# lumysens.net
KiCad netlist of a schematic drawn in EAGLE
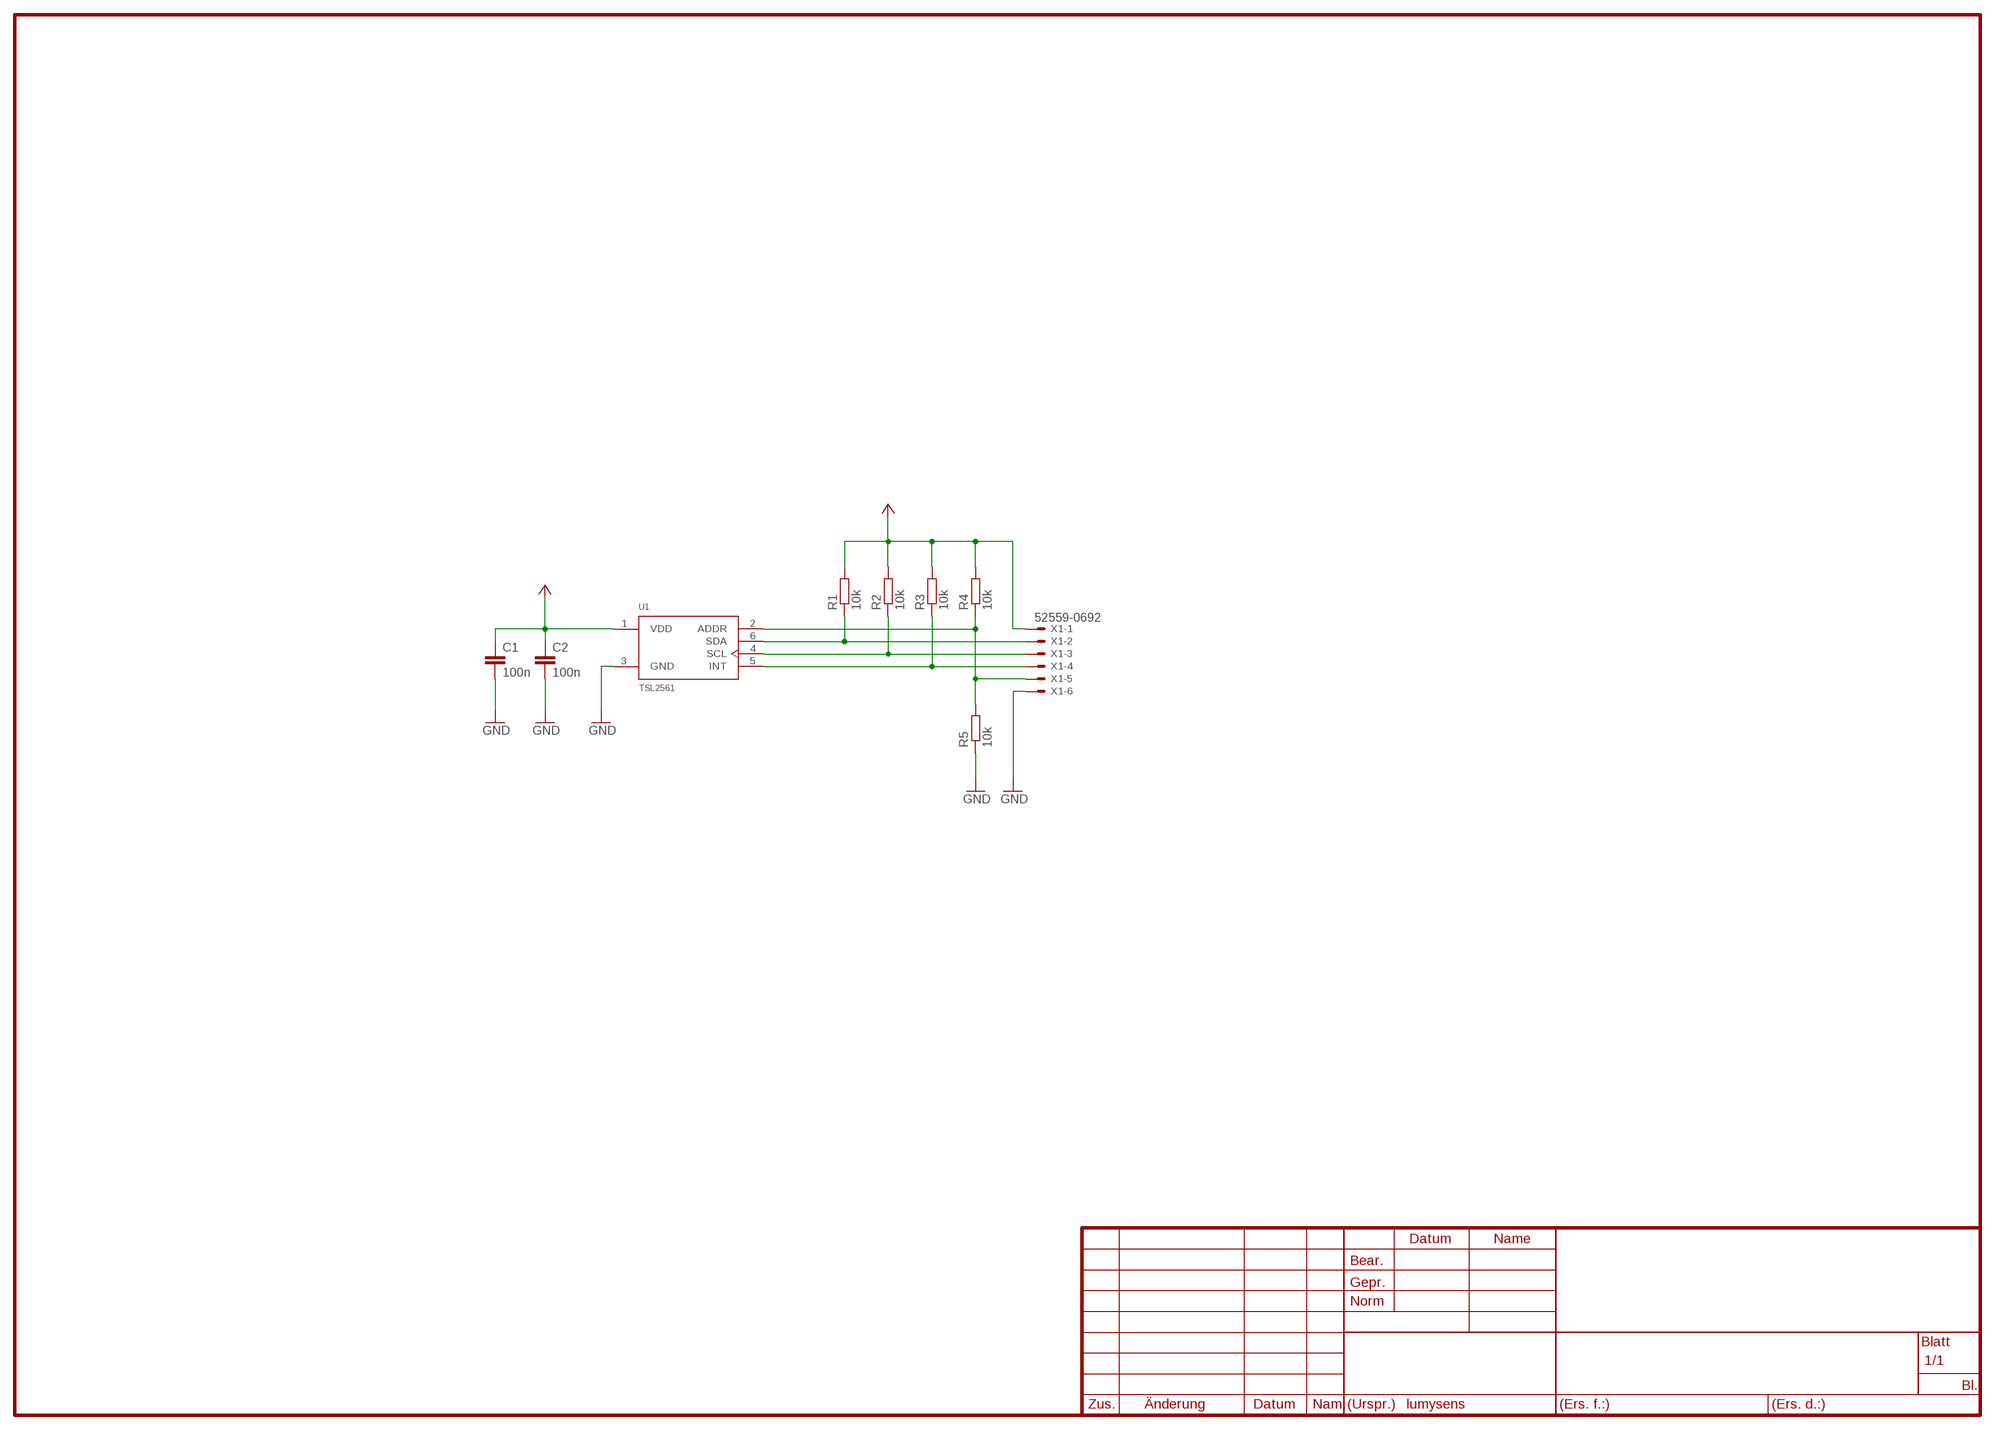
[diagram p0: schematic, sheet 1]

(export (version "E")
  (design (tool "Eeschema 10.0.6"))
  (components
    (comp (ref "C1")
      (value "100n")
      (footprint "eagle-import:C0603")
      (libsource (lib "eagle-import") (part "C-EUC0603"))
    )
    (comp (ref "C2")
      (value "100n")
      (footprint "eagle-import:C0603")
      (libsource (lib "eagle-import") (part "C-EUC0603"))
    )
    (comp (ref "R1")
      (value "10k")
      (footprint "eagle-import:R0603")
      (libsource (lib "eagle-import") (part "R-EU_R0603"))
    )
    (comp (ref "R2")
      (value "10k")
      (footprint "eagle-import:R0603")
      (libsource (lib "eagle-import") (part "R-EU_R0603"))
    )
    (comp (ref "R3")
      (value "10k")
      (footprint "eagle-import:R0603")
      (libsource (lib "eagle-import") (part "R-EU_R0603"))
    )
    (comp (ref "R4")
      (value "10k")
      (footprint "eagle-import:R0603")
      (libsource (lib "eagle-import") (part "R-EU_R0603"))
    )
    (comp (ref "R5")
      (value "10k")
      (footprint "eagle-import:R0603")
      (libsource (lib "eagle-import") (part "R-EU_R0603"))
    )
    (comp (ref "U1")
      (value "TSL2561")
      (footprint "eagle-import:TMB-6")
      (libsource (lib "eagle-import") (part "TSL2561"))
    )
    (comp (ref "X1")
      (value "52559-0692")
      (footprint "eagle-import:52559-0692")
      (libsource (lib "eagle-import") (part "52559-0692"))
    )
  )
  (nets
    (net (code "1") (name "GND") (class "Default")
      (node (ref "C1") (pin "2") (pinfunction "2_2") (pintype "passive"))
      (node (ref "C2") (pin "2") (pinfunction "2_2") (pintype "passive"))
      (node (ref "R5") (pin "1") (pinfunction "1_1") (pintype "passive"))
      (node (ref "U1") (pin "3") (pinfunction "GND_3") (pintype "power_in"))
      (node (ref "X1") (pin "6") (pinfunction "S_6") (pintype "passive"))
    )
    (net (code "2") (name "Net-(U1-ADDR)") (class "Default")
      (node (ref "R4") (pin "1") (pinfunction "1_1") (pintype "passive"))
      (node (ref "R5") (pin "2") (pinfunction "2_2") (pintype "passive"))
      (node (ref "U1") (pin "2") (pinfunction "ADDR_2") (pintype "input"))
      (node (ref "X1") (pin "5") (pinfunction "S_5") (pintype "passive"))
    )
    (net (code "3") (name "Net-(U1-INT)") (class "Default")
      (node (ref "R3") (pin "1") (pinfunction "1_1") (pintype "passive"))
      (node (ref "U1") (pin "5") (pinfunction "INT_5") (pintype "output"))
      (node (ref "X1") (pin "4") (pinfunction "S_4") (pintype "passive"))
    )
    (net (code "4") (name "Net-(U1-SCL)") (class "Default")
      (node (ref "R2") (pin "1") (pinfunction "1_1") (pintype "passive"))
      (node (ref "U1") (pin "4") (pinfunction "SCL_4") (pintype "input"))
      (node (ref "X1") (pin "3") (pinfunction "S_3") (pintype "passive"))
    )
    (net (code "5") (name "Net-(U1-SDA)") (class "Default")
      (node (ref "R1") (pin "1") (pinfunction "1_1") (pintype "passive"))
      (node (ref "U1") (pin "6") (pinfunction "SDA_6") (pintype "bidirectional"))
      (node (ref "X1") (pin "2") (pinfunction "S_2") (pintype "passive"))
    )
    (net (code "6") (name "VCC") (class "Default")
      (node (ref "C1") (pin "1") (pinfunction "1_1") (pintype "passive"))
      (node (ref "C2") (pin "1") (pinfunction "1_1") (pintype "passive"))
      (node (ref "R1") (pin "2") (pinfunction "2_2") (pintype "passive"))
      (node (ref "R2") (pin "2") (pinfunction "2_2") (pintype "passive"))
      (node (ref "R3") (pin "2") (pinfunction "2_2") (pintype "passive"))
      (node (ref "R4") (pin "2") (pinfunction "2_2") (pintype "passive"))
      (node (ref "U1") (pin "1") (pinfunction "VDD_1") (pintype "power_in"))
      (node (ref "X1") (pin "1") (pinfunction "S_1") (pintype "passive"))
    )
  )
)
